# adalogger_featherwing.net
KiCad netlist of a schematic drawn in EAGLE
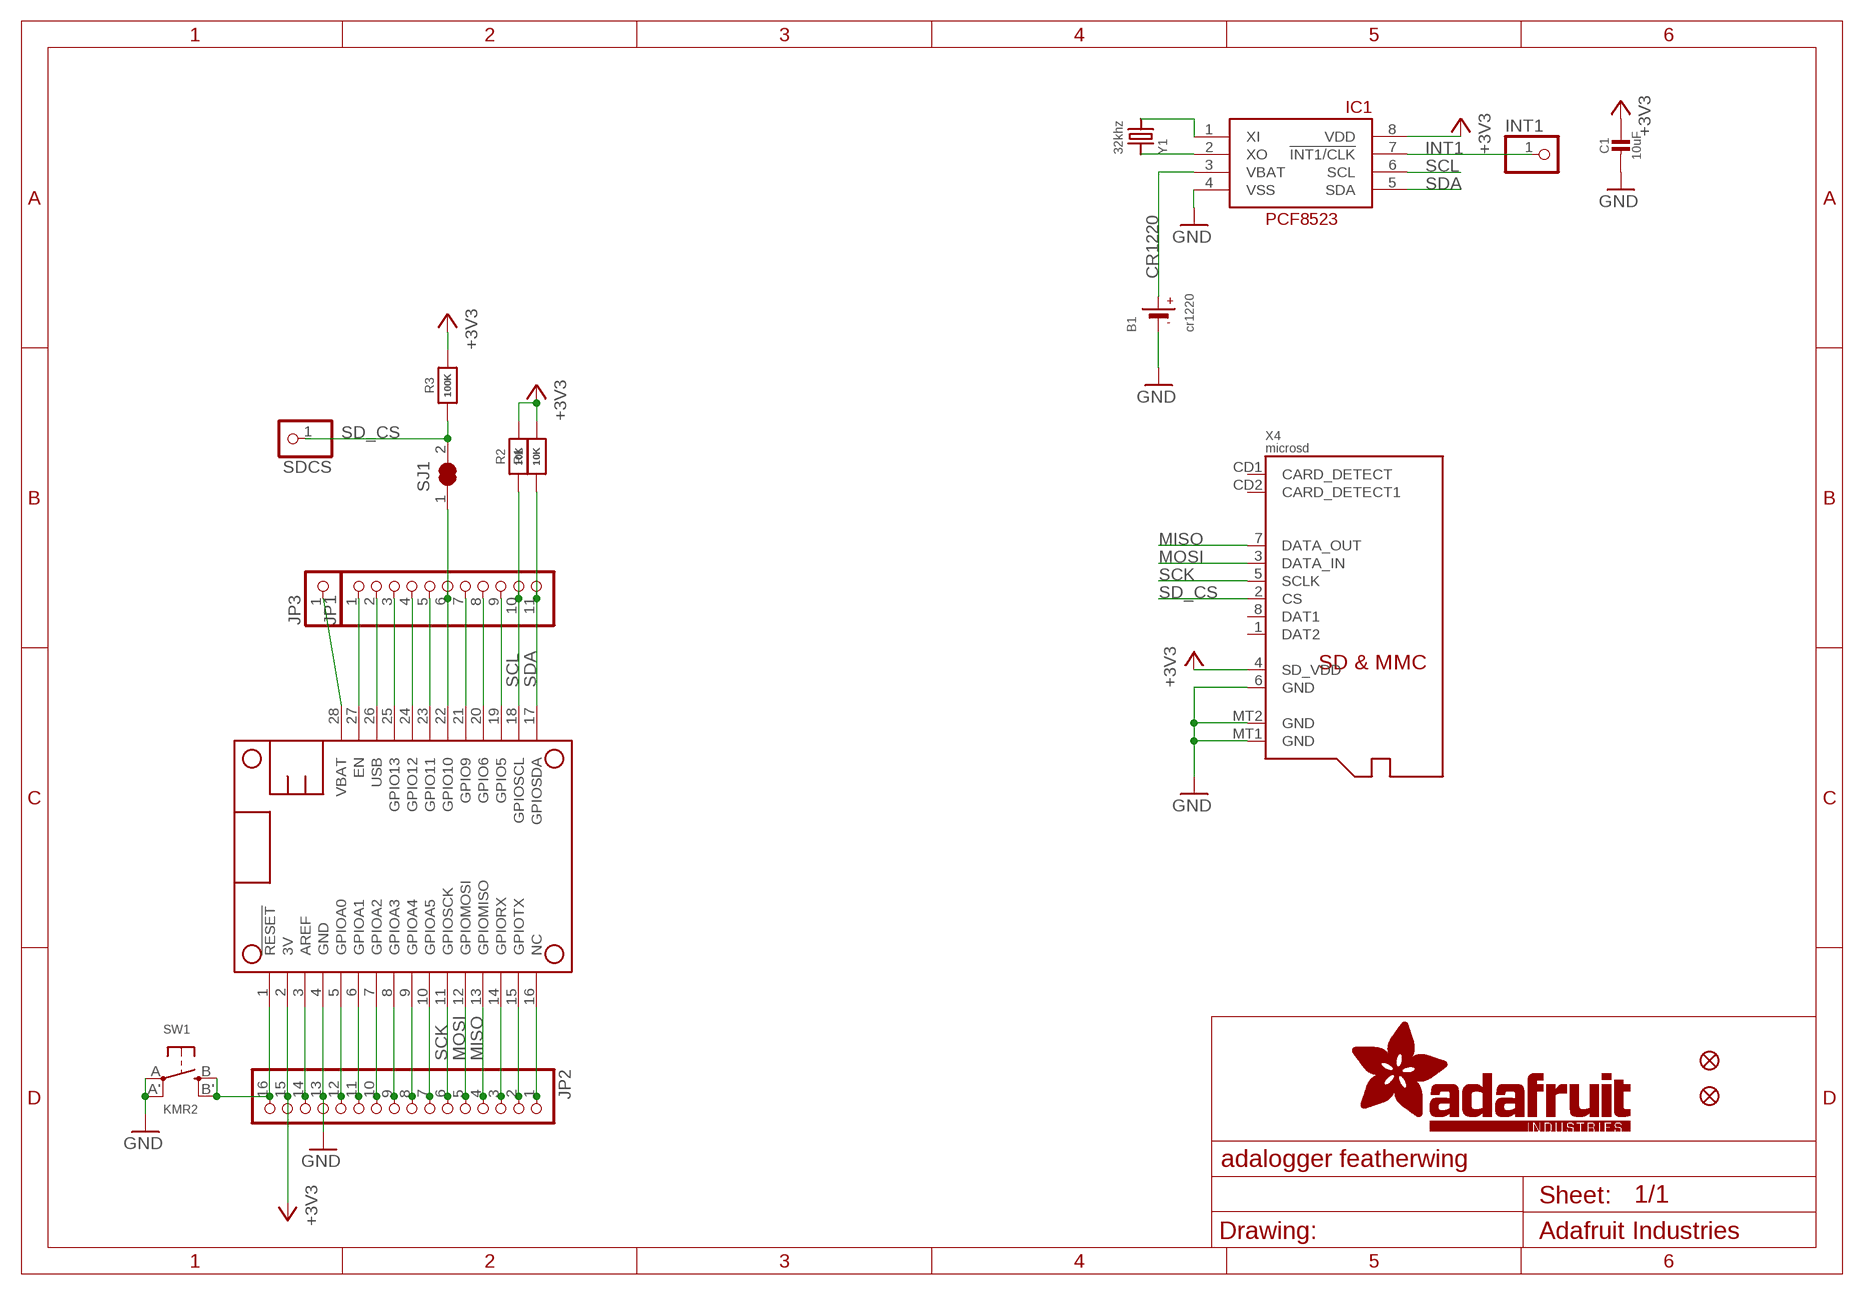
[diagram p0: schematic, sheet 1]

(export (version "E")
  (design (tool "Eeschema 10.0.6"))
  (components
    (comp (ref "B1")
      (value "cr1220")
      (footprint "eagle-import:CR1220-2")
      (libsource (lib "eagle-import") (part "BATTERYCR1220_2"))
    )
    (comp (ref "C1")
      (value "10uF")
      (footprint "eagle-import:0805-NO")
      (libsource (lib "eagle-import") (part "CAP_CERAMIC0805-NOOUTLINE"))
    )
    (comp (ref "FID1")
      (value "FIDUCIAL\"\"")
      (footprint "eagle-import:FIDUCIAL_1MM")
      (libsource (lib "eagle-import") (part "FIDUCIAL{dblquote}{dblquote}"))
    )
    (comp (ref "FID2")
      (value "FIDUCIAL\"\"")
      (footprint "eagle-import:FIDUCIAL_1MM")
      (libsource (lib "eagle-import") (part "FIDUCIAL{dblquote}{dblquote}"))
    )
    (comp (ref "IC1")
      (value "RTC_PCF8523T")
      (footprint "eagle-import:SOIC8_150MIL")
      (libsource (lib "eagle-import") (part "RTC_PCF8523T"))
    )
    (comp (ref "INT1")
      (value "HEADER-1X1ROUND")
      (footprint "eagle-import:1X01_ROUND")
      (libsource (lib "eagle-import") (part "HEADER-1X1ROUND"))
    )
    (comp (ref "JP1")
      (value "HEADER-1X11")
      (footprint "eagle-import:1X11_ROUND")
      (libsource (lib "eagle-import") (part "HEADER-1X11"))
    )
    (comp (ref "JP2")
      (value "HEADER-1X16ROUND")
      (footprint "eagle-import:1X16_ROUND")
      (libsource (lib "eagle-import") (part "HEADER-1X16ROUND"))
    )
    (comp (ref "JP3")
      (value "HEADER-1X1ROUND")
      (footprint "eagle-import:1X01_ROUND")
      (libsource (lib "eagle-import") (part "HEADER-1X1ROUND"))
    )
    (comp (ref "MS1")
      (value "FEATHERWING_NODIM")
      (footprint "eagle-import:FEATHERWING_DIM")
      (libsource (lib "eagle-import") (part "FEATHERWING_NODIM"))
    )
    (comp (ref "R1")
      (value "10K")
      (footprint "eagle-import:0805-NO")
      (libsource (lib "eagle-import") (part "RESISTOR0805_NOOUTLINE"))
    )
    (comp (ref "R2")
      (value "10K")
      (footprint "eagle-import:0805-NO")
      (libsource (lib "eagle-import") (part "RESISTOR0805_NOOUTLINE"))
    )
    (comp (ref "R3")
      (value "100K")
      (footprint "eagle-import:0805-NO")
      (libsource (lib "eagle-import") (part "RESISTOR0805_NOOUTLINE"))
    )
    (comp (ref "SDCS")
      (value "HEADER-1X1ROUND")
      (footprint "eagle-import:1X01_ROUND")
      (libsource (lib "eagle-import") (part "HEADER-1X1ROUND"))
    )
    (comp (ref "SJ1")
      (value "SOLDERJUMPER_CLOSED")
      (footprint "eagle-import:SOLDERJUMPER_CLOSEDWIRE")
      (libsource (lib "eagle-import") (part "SOLDERJUMPER_CLOSED"))
    )
    (comp (ref "SW1")
      (value "KMR2")
      (footprint "eagle-import:BTN_KMR2_4.6X2.8")
      (libsource (lib "eagle-import") (part "SWITCH_TACT_SMT4.6X2.8"))
    )
    (comp (ref "X4")
      (value "microsd")
      (footprint "eagle-import:MICROSD")
      (libsource (lib "eagle-import") (part "MICROSD"))
    )
    (comp (ref "Y1")
      (value "32khz")
      (footprint "eagle-import:CRYSTAL_8X3.8")
      (libsource (lib "eagle-import") (part "CRYSTAL8.0X3.8"))
    )
  )
  (nets
    (net (code "1") (name "+3V3") (class "Default")
      (node (ref "C1") (pin "1") (pinfunction "1_1") (pintype "passive"))
      (node (ref "IC1") (pin "8") (pinfunction "VDD_8") (pintype "power_in"))
      (node (ref "JP2") (pin "15") (pinfunction "15_15") (pintype "passive"))
      (node (ref "MS1") (pin "2") (pinfunction "3V_2") (pintype "power_in"))
      (node (ref "R1") (pin "2") (pinfunction "2_2") (pintype "passive"))
      (node (ref "R2") (pin "2") (pinfunction "2_2") (pintype "passive"))
      (node (ref "R3") (pin "2") (pinfunction "2_2") (pintype "passive"))
      (node (ref "X4") (pin "4") (pinfunction "SD_VDD_4") (pintype "power_in"))
    )
    (net (code "2") (name "/CR1220") (class "Default")
      (node (ref "B1") (pin "+") (pinfunction "+_+") (pintype "passive"))
      (node (ref "IC1") (pin "3") (pinfunction "VBAT_3") (pintype "power_in"))
    )
    (net (code "3") (name "/INT1") (class "Default")
      (node (ref "IC1") (pin "7") (pinfunction "~{INT1/CLK}_7") (pintype "output"))
      (node (ref "INT1") (pin "1") (pinfunction "1_1") (pintype "passive"))
    )
    (net (code "4") (name "/MISO") (class "Default")
      (node (ref "JP2") (pin "4") (pinfunction "4_4") (pintype "passive"))
      (node (ref "MS1") (pin "13") (pinfunction "GPIOMISO_13") (pintype "bidirectional"))
      (node (ref "X4") (pin "7") (pinfunction "DATA_OUT_7") (pintype "output"))
    )
    (net (code "5") (name "/MOSI") (class "Default")
      (node (ref "JP2") (pin "5") (pinfunction "5_5") (pintype "passive"))
      (node (ref "MS1") (pin "12") (pinfunction "GPIOMOSI_12") (pintype "bidirectional"))
      (node (ref "X4") (pin "3") (pinfunction "DATA_IN_3") (pintype "input"))
    )
    (net (code "6") (name "/SCK") (class "Default")
      (node (ref "JP2") (pin "6") (pinfunction "6_6") (pintype "passive"))
      (node (ref "MS1") (pin "11") (pinfunction "GPIOSCK_11") (pintype "bidirectional"))
      (node (ref "X4") (pin "5") (pinfunction "SCLK_5") (pintype "input"))
    )
    (net (code "7") (name "/SCL") (class "Default")
      (node (ref "IC1") (pin "6") (pinfunction "SCL_6") (pintype "bidirectional"))
      (node (ref "JP1") (pin "10") (pinfunction "10_10") (pintype "passive"))
      (node (ref "MS1") (pin "18") (pinfunction "GPIOSCL_18") (pintype "bidirectional"))
      (node (ref "R2") (pin "1") (pinfunction "1_1") (pintype "passive"))
    )
    (net (code "8") (name "/SDA") (class "Default")
      (node (ref "IC1") (pin "5") (pinfunction "SDA_5") (pintype "bidirectional"))
      (node (ref "JP1") (pin "11") (pinfunction "11_11") (pintype "passive"))
      (node (ref "MS1") (pin "17") (pinfunction "GPIOSDA_17") (pintype "bidirectional"))
      (node (ref "R1") (pin "1") (pinfunction "1_1") (pintype "passive"))
    )
    (net (code "9") (name "/SD_CS") (class "Default")
      (node (ref "R3") (pin "1") (pinfunction "1_1") (pintype "passive"))
      (node (ref "SDCS") (pin "1") (pinfunction "1_1") (pintype "passive"))
      (node (ref "SJ1") (pin "2") (pinfunction "2_2") (pintype "passive"))
      (node (ref "X4") (pin "2") (pinfunction "CS_2") (pintype "input"))
    )
    (net (code "10") (name "GND") (class "Default")
      (node (ref "B1") (pin "-") (pinfunction "-_-") (pintype "passive"))
      (node (ref "C1") (pin "2") (pinfunction "2_2") (pintype "passive"))
      (node (ref "IC1") (pin "4") (pinfunction "VSS_4") (pintype "power_in"))
      (node (ref "JP2") (pin "13") (pinfunction "13_13") (pintype "passive"))
      (node (ref "MS1") (pin "4") (pinfunction "GND_4") (pintype "power_in"))
      (node (ref "SW1") (pin "A") (pinfunction "P_A") (pintype "passive"))
      (node (ref "SW1") (pin "A'") (pinfunction "P1_A'") (pintype "passive"))
      (node (ref "X4") (pin "6") (pinfunction "GND_6") (pintype "power_in"))
      (node (ref "X4") (pin "MT1") (pinfunction "GND_MT1") (pintype "power_in"))
      (node (ref "X4") (pin "MT2") (pinfunction "GND_MT2") (pintype "power_in"))
    )
    (net (code "11") (name "Net-(IC1-XI)") (class "Default")
      (node (ref "IC1") (pin "1") (pinfunction "XI_1") (pintype "input"))
      (node (ref "Y1") (pin "P$4") (pinfunction "2_P$4") (pintype "passive"))
    )
    (net (code "12") (name "Net-(IC1-XO)") (class "Default")
      (node (ref "IC1") (pin "2") (pinfunction "XO_2") (pintype "output"))
      (node (ref "Y1") (pin "P$1") (pinfunction "1_P$1") (pintype "passive"))
    )
    (net (code "13") (name "Net-(MS1-AREF)") (class "Default")
      (node (ref "JP2") (pin "14") (pinfunction "14_14") (pintype "passive"))
      (node (ref "MS1") (pin "3") (pinfunction "AREF_3") (pintype "passive"))
    )
    (net (code "14") (name "Net-(MS1-EN)") (class "Default")
      (node (ref "JP1") (pin "1") (pinfunction "1_1") (pintype "passive"))
      (node (ref "MS1") (pin "27") (pinfunction "EN_27") (pintype "passive"))
    )
    (net (code "15") (name "Net-(MS1-GPIO5)") (class "Default")
      (node (ref "JP1") (pin "9") (pinfunction "9_9") (pintype "passive"))
      (node (ref "MS1") (pin "19") (pinfunction "GPIO5_19") (pintype "bidirectional"))
    )
    (net (code "16") (name "Net-(MS1-GPIO6)") (class "Default")
      (node (ref "JP1") (pin "8") (pinfunction "8_8") (pintype "passive"))
      (node (ref "MS1") (pin "20") (pinfunction "GPIO6_20") (pintype "bidirectional"))
    )
    (net (code "17") (name "Net-(MS1-GPIO9)") (class "Default")
      (node (ref "JP1") (pin "7") (pinfunction "7_7") (pintype "passive"))
      (node (ref "MS1") (pin "21") (pinfunction "GPIO9_21") (pintype "bidirectional"))
    )
    (net (code "18") (name "Net-(MS1-GPIO10)") (class "Default")
      (node (ref "JP1") (pin "6") (pinfunction "6_6") (pintype "passive"))
      (node (ref "MS1") (pin "22") (pinfunction "GPIO10_22") (pintype "bidirectional"))
      (node (ref "SJ1") (pin "1") (pinfunction "1_1") (pintype "passive"))
    )
    (net (code "19") (name "Net-(MS1-GPIO11)") (class "Default")
      (node (ref "JP1") (pin "5") (pinfunction "5_5") (pintype "passive"))
      (node (ref "MS1") (pin "23") (pinfunction "GPIO11_23") (pintype "bidirectional"))
    )
    (net (code "20") (name "Net-(MS1-GPIO12)") (class "Default")
      (node (ref "JP1") (pin "4") (pinfunction "4_4") (pintype "passive"))
      (node (ref "MS1") (pin "24") (pinfunction "GPIO12_24") (pintype "bidirectional"))
    )
    (net (code "21") (name "Net-(MS1-GPIO13)") (class "Default")
      (node (ref "JP1") (pin "3") (pinfunction "3_3") (pintype "passive"))
      (node (ref "MS1") (pin "25") (pinfunction "GPIO13_25") (pintype "bidirectional"))
    )
    (net (code "22") (name "Net-(MS1-GPIOA0)") (class "Default")
      (node (ref "JP2") (pin "12") (pinfunction "12_12") (pintype "passive"))
      (node (ref "MS1") (pin "5") (pinfunction "GPIOA0_5") (pintype "bidirectional"))
    )
    (net (code "23") (name "Net-(MS1-GPIOA1)") (class "Default")
      (node (ref "JP2") (pin "11") (pinfunction "11_11") (pintype "passive"))
      (node (ref "MS1") (pin "6") (pinfunction "GPIOA1_6") (pintype "bidirectional"))
    )
    (net (code "24") (name "Net-(MS1-GPIOA2)") (class "Default")
      (node (ref "JP2") (pin "10") (pinfunction "10_10") (pintype "passive"))
      (node (ref "MS1") (pin "7") (pinfunction "GPIOA2_7") (pintype "bidirectional"))
    )
    (net (code "25") (name "Net-(MS1-GPIOA3)") (class "Default")
      (node (ref "JP2") (pin "9") (pinfunction "9_9") (pintype "passive"))
      (node (ref "MS1") (pin "8") (pinfunction "GPIOA3_8") (pintype "bidirectional"))
    )
    (net (code "26") (name "Net-(MS1-GPIOA4)") (class "Default")
      (node (ref "JP2") (pin "8") (pinfunction "8_8") (pintype "passive"))
      (node (ref "MS1") (pin "9") (pinfunction "GPIOA4_9") (pintype "bidirectional"))
    )
    (net (code "27") (name "Net-(MS1-GPIOA5)") (class "Default")
      (node (ref "JP2") (pin "7") (pinfunction "7_7") (pintype "passive"))
      (node (ref "MS1") (pin "10") (pinfunction "GPIOA5_10") (pintype "bidirectional"))
    )
    (net (code "28") (name "Net-(MS1-GPIORX)") (class "Default")
      (node (ref "JP2") (pin "3") (pinfunction "3_3") (pintype "passive"))
      (node (ref "MS1") (pin "14") (pinfunction "GPIORX_14") (pintype "bidirectional"))
    )
    (net (code "29") (name "Net-(MS1-GPIOTX)") (class "Default")
      (node (ref "JP2") (pin "2") (pinfunction "2_2") (pintype "passive"))
      (node (ref "MS1") (pin "15") (pinfunction "GPIOTX_15") (pintype "bidirectional"))
    )
    (net (code "30") (name "Net-(MS1-NC)") (class "Default")
      (node (ref "JP2") (pin "1") (pinfunction "1_1") (pintype "passive"))
      (node (ref "MS1") (pin "16") (pinfunction "NC_16") (pintype "passive"))
    )
    (net (code "31") (name "Net-(MS1-USB)") (class "Default")
      (node (ref "JP1") (pin "2") (pinfunction "2_2") (pintype "passive"))
      (node (ref "MS1") (pin "26") (pinfunction "USB_26") (pintype "power_in"))
    )
    (net (code "32") (name "Net-(MS1-VBAT)") (class "Default")
      (node (ref "JP3") (pin "1") (pinfunction "1_1") (pintype "passive"))
      (node (ref "MS1") (pin "28") (pinfunction "VBAT_28") (pintype "power_in"))
    )
    (net (code "33") (name "Net-(MS1-~{RESET})") (class "Default")
      (node (ref "JP2") (pin "16") (pinfunction "16_16") (pintype "passive"))
      (node (ref "MS1") (pin "1") (pinfunction "~{RESET}_1") (pintype "input"))
      (node (ref "SW1") (pin "B") (pinfunction "S_B") (pintype "passive"))
      (node (ref "SW1") (pin "B'") (pinfunction "S1_B'") (pintype "passive"))
    )
    (net (code "34") (name "unconnected-(X4-CARD_DETECT-PadCD1)") (class "Default")
      (node (ref "X4") (pin "CD1") (pinfunction "CARD_DETECT_CD1") (pintype "passive"))
    )
    (net (code "35") (name "unconnected-(X4-CARD_DETECT1-PadCD2)") (class "Default")
      (node (ref "X4") (pin "CD2") (pinfunction "CARD_DETECT1_CD2") (pintype "passive"))
    )
    (net (code "36") (name "unconnected-(X4-DAT1-Pad8)") (class "Default")
      (node (ref "X4") (pin "8") (pinfunction "DAT1_8") (pintype "bidirectional"))
    )
    (net (code "37") (name "unconnected-(X4-DAT2-Pad1)") (class "Default")
      (node (ref "X4") (pin "1") (pinfunction "DAT2_1") (pintype "bidirectional"))
    )
  )
)
